# GW-RS485-V41-007.net
KiCad netlist of a schematic drawn in EAGLE
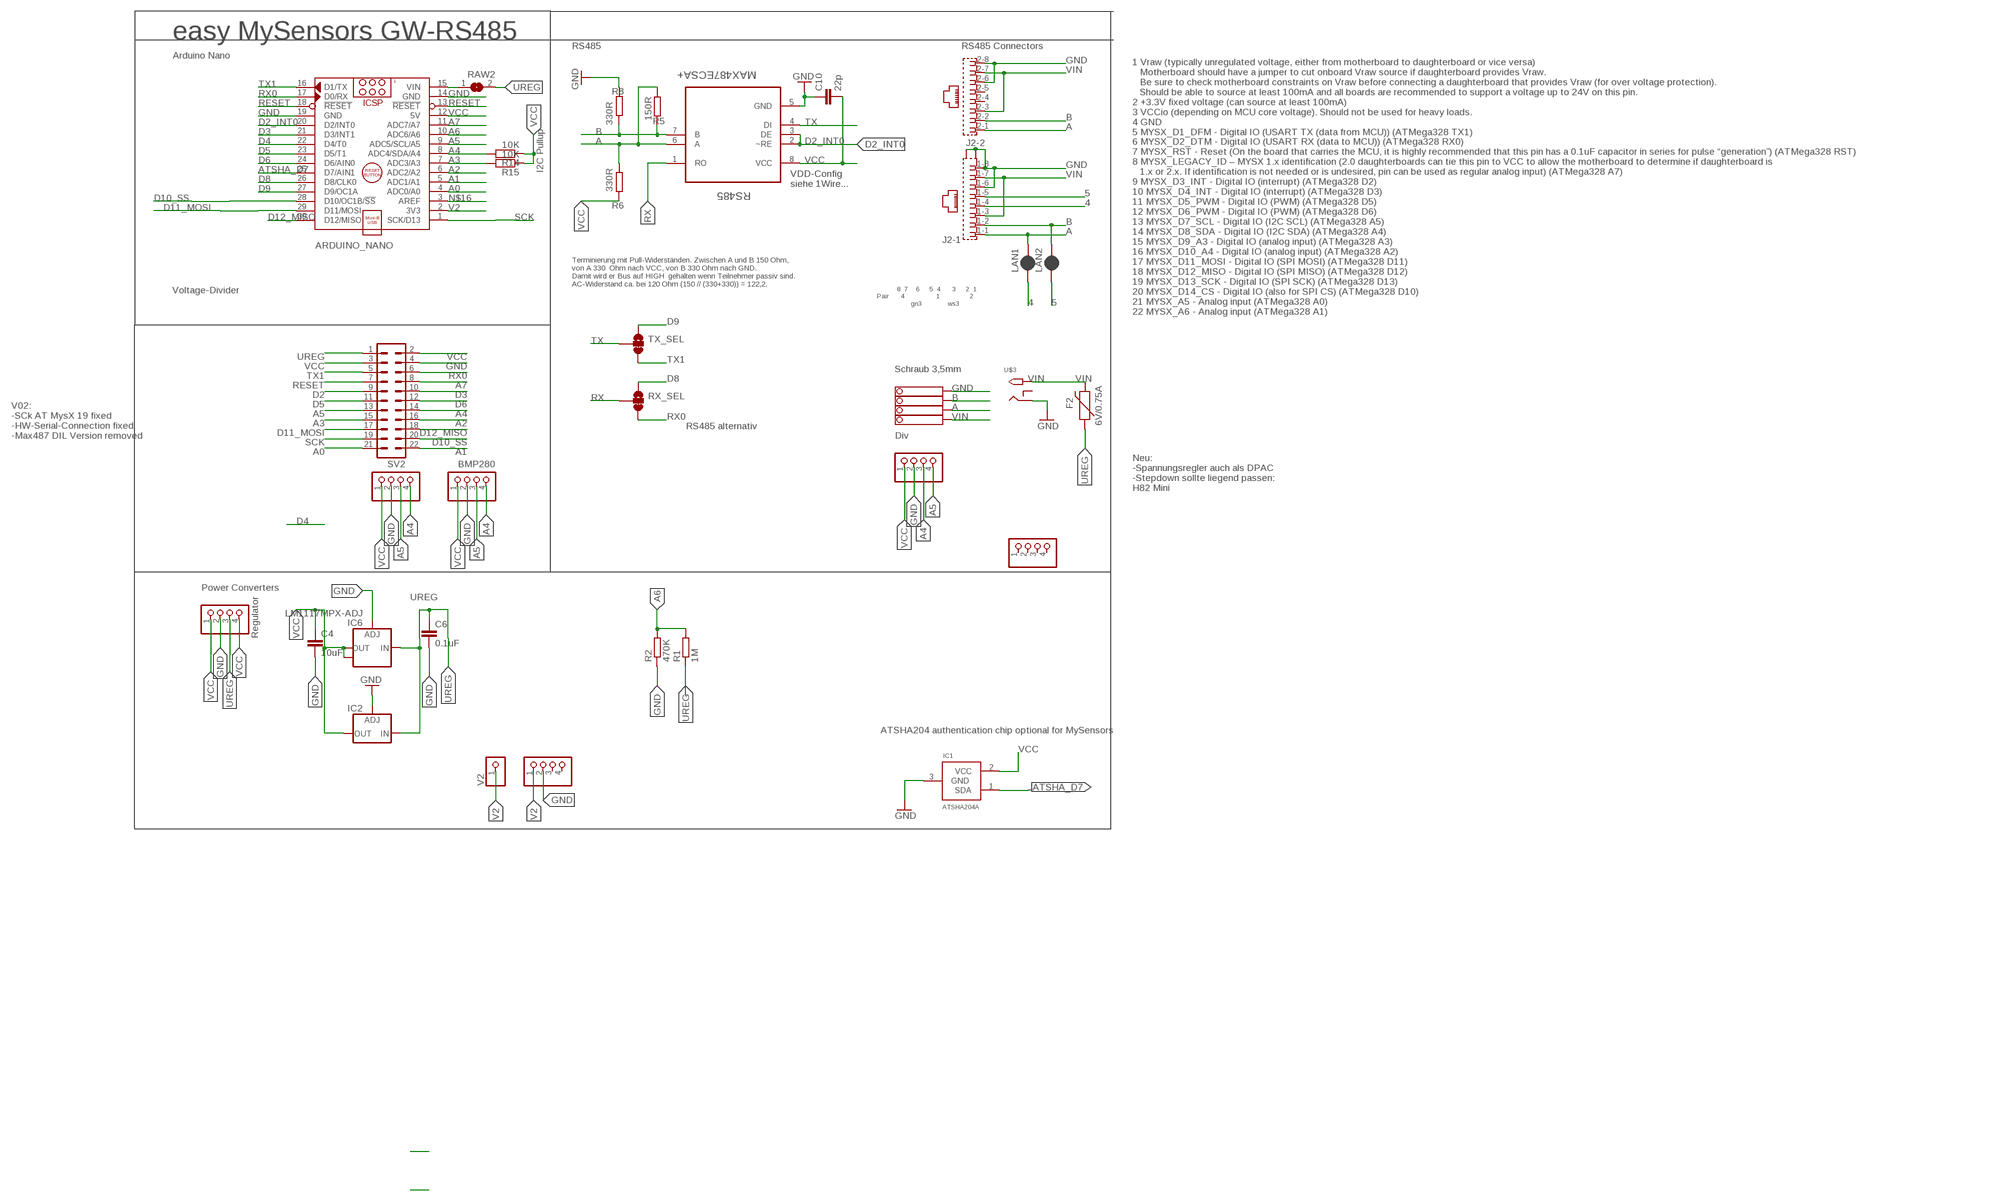
[diagram p0: schematic, sheet 1]

(export (version "E")
  (design (tool "Eeschema 10.0.6"))
  (components
    (comp (ref "ARDUINO_NANO")
      (value "ARDUINO_NANO_OHNE-BOHR")
      (footprint "eagle-import:ARDUINO_NANO")
      (libsource (lib "eagle-import") (part "ARDUINO_NANO_OHNE-BOHR"))
    )
    (comp (ref "BH1750")
      (value "PINHD-1X04_2.54-S")
      (footprint "eagle-import:1X04-S")
      (libsource (lib "eagle-import") (part "PINHD-1X04_2.54-S"))
    )
    (comp (ref "C4")
      (value "10uF")
      (footprint "eagle-import:C1210")
      (libsource (lib "eagle-import") (part "C-EUC1210"))
    )
    (comp (ref "C6")
      (value "0.1uF")
      (footprint "eagle-import:C1206")
      (libsource (lib "eagle-import") (part "C-EUC1206"))
    )
    (comp (ref "C10")
      (value "22p")
      (footprint "eagle-import:C0805")
      (libsource (lib "eagle-import") (part "C-EUC0805"))
    )
    (comp (ref "F2")
      (value "6V/0.75A")
      (footprint "eagle-import:1206")
      (libsource (lib "eagle-import") (part "PPTC_THREE-QUARTER-AMP"))
    )
    (comp (ref "I2C-1")
      (value "PINHD-1X04_2.54-S")
      (footprint "eagle-import:1X04-S")
      (libsource (lib "eagle-import") (part "PINHD-1X04_2.54-S"))
    )
    (comp (ref "I2C-2")
      (value "PINHD-1X04_2.54-S")
      (footprint "eagle-import:1X04-S")
      (libsource (lib "eagle-import") (part "PINHD-1X04_2.54-S"))
    )
    (comp (ref "IC1")
      (value "ATSHA204A")
      (footprint "eagle-import:SOT23")
      (libsource (lib "eagle-import") (part "ATSHA204A"))
    )
    (comp (ref "IC2")
      (value "LD117ADT50TR")
      (footprint "eagle-import:DPACK")
      (libsource (lib "eagle-import") (part "LD117A?DT50TR"))
    )
    (comp (ref "IC6")
      (value "LM1117MPX-ADJ")
      (footprint "eagle-import:SOT223")
      (libsource (lib "eagle-import") (part "LM1117MPX-ADJ"))
    )
    (comp (ref "J2")
      (value "RJ45_2X_S")
      (footprint "eagle-import:RJ45_2X_S")
      (libsource (lib "eagle-import") (part "RJ45_2X_S"))
    )
    (comp (ref "JP2")
      (value "PINHD-1X04_2.54-S")
      (footprint "eagle-import:1X04-S")
      (libsource (lib "eagle-import") (part "PINHD-1X04_2.54-S"))
    )
    (comp (ref "LAN1")
      (value "JUMPER-SMT_2_NC_PASTE_SILK")
      (footprint "eagle-import:SMT-JUMPER_2_NC_PASTE_SILK")
      (libsource (lib "eagle-import") (part "JUMPER-SMT_2_NC_PASTE_SILK"))
    )
    (comp (ref "LAN2")
      (value "JUMPER-SMT_2_NC_PASTE_SILK")
      (footprint "eagle-import:SMT-JUMPER_2_NC_PASTE_SILK")
      (libsource (lib "eagle-import") (part "JUMPER-SMT_2_NC_PASTE_SILK"))
    )
    (comp (ref "R1")
      (value "1M")
      (footprint "eagle-import:R0805")
      (libsource (lib "eagle-import") (part "R-EU_R0805"))
    )
    (comp (ref "R2")
      (value "470K")
      (footprint "eagle-import:R0805")
      (libsource (lib "eagle-import") (part "R-EU_R0805"))
    )
    (comp (ref "R5")
      (value "150R")
      (footprint "eagle-import:R0805")
      (libsource (lib "eagle-import") (part "R-EU_R0805"))
    )
    (comp (ref "R6")
      (value "330R")
      (footprint "eagle-import:R0805")
      (libsource (lib "eagle-import") (part "R-EU_R0805"))
    )
    (comp (ref "R8")
      (value "330R")
      (footprint "eagle-import:R0805")
      (libsource (lib "eagle-import") (part "R-EU_R0805"))
    )
    (comp (ref "R14")
      (value "10K")
      (footprint "eagle-import:R0805")
      (libsource (lib "eagle-import") (part "R-EU_R0805"))
    )
    (comp (ref "R15")
      (value "10K")
      (footprint "eagle-import:R0805")
      (libsource (lib "eagle-import") (part "R-EU_R0805"))
    )
    (comp (ref "RAW2")
      (value "SJ")
      (footprint "eagle-import:SJ")
      (libsource (lib "eagle-import") (part "SJ"))
    )
    (comp (ref "RS485")
      (value "MAX487ECSA+")
      (footprint "eagle-import:SOIC127P600X175-8N")
      (libsource (lib "eagle-import") (part "MAX487ECSA+"))
    )
    (comp (ref "RX_SEL")
      (value "JUMPER-SMT_3_1-NC_TRACE_SILK")
      (footprint "eagle-import:SMT-JUMPER_3_1-NC_TRACE_SILK")
      (libsource (lib "eagle-import") (part "JUMPER-SMT_3_1-NC_TRACE_SILK"))
    )
    (comp (ref "STEPDWN")
      (value "PINHD-1X04_2.54-S")
      (footprint "eagle-import:1X04-S")
      (libsource (lib "eagle-import") (part "PINHD-1X04_2.54-S"))
    )
    (comp (ref "SV2")
      (value "MA11-2")
      (footprint "eagle-import:MA11-2")
      (libsource (lib "eagle-import") (part "MA11-2"))
    )
    (comp (ref "TX_SEL")
      (value "JUMPER-SMT_3_1-NC_TRACE_SILK")
      (footprint "eagle-import:SMT-JUMPER_3_1-NC_TRACE_SILK")
      (libsource (lib "eagle-import") (part "JUMPER-SMT_3_1-NC_TRACE_SILK"))
    )
    (comp (ref "U$3")
      (value "2.1MMJACKTHM")
      (footprint "eagle-import:PJ-102A")
      (libsource (lib "eagle-import") (part "2.1MMJACKTHM"))
    )
    (comp (ref "V2")
      (value "PINHD-1X1")
      (footprint "eagle-import:1X01")
      (libsource (lib "eagle-import") (part "PINHD-1X1"))
    )
    (comp (ref "V2-")
      (value "PINHD-1X04_2.54-S")
      (footprint "eagle-import:1X04-S")
      (libsource (lib "eagle-import") (part "PINHD-1X04_2.54-S"))
    )
    (comp (ref "X4")
      (value "1751264")
      (footprint "eagle-import:1751264")
      (libsource (lib "eagle-import") (part "1751264"))
    )
  )
  (nets
    (net (code "1") (name "/4") (class "Default")
      (node (ref "J2") (pin "1-4") (pinfunction "4_1-4") (pintype "passive"))
      (node (ref "LAN1") (pin "1") (pinfunction "1_1") (pintype "passive"))
    )
    (net (code "2") (name "/5") (class "Default")
      (node (ref "J2") (pin "1-5") (pinfunction "5_1-5") (pintype "passive"))
      (node (ref "LAN2") (pin "1") (pinfunction "1_1") (pintype "passive"))
    )
    (net (code "3") (name "/A") (class "Default")
      (node (ref "J2") (pin "1-1") (pinfunction "1_1-1") (pintype "passive"))
      (node (ref "J2") (pin "2-1") (pinfunction "1_2-1") (pintype "passive"))
      (node (ref "LAN1") (pin "2") (pinfunction "2_2") (pintype "passive"))
      (node (ref "R5") (pin "1") (pinfunction "1_1") (pintype "passive"))
      (node (ref "R6") (pin "2") (pinfunction "2_2") (pintype "passive"))
      (node (ref "RS485") (pin "6") (pinfunction "A_6") (pintype "bidirectional"))
      (node (ref "X4") (pin "2") (pinfunction "K_2") (pintype "passive"))
    )
    (net (code "4") (name "/A0") (class "Default")
      (node (ref "ARDUINO_NANO") (pin "4") (pinfunction "ADC0/A0_4") (pintype "bidirectional"))
      (node (ref "SV2") (pin "21") (pinfunction "21_21") (pintype "passive"))
    )
    (net (code "5") (name "/A1") (class "Default")
      (node (ref "ARDUINO_NANO") (pin "5") (pinfunction "ADC1/A1_5") (pintype "bidirectional"))
      (node (ref "SV2") (pin "22") (pinfunction "22_22") (pintype "passive"))
    )
    (net (code "6") (name "/A2") (class "Default")
      (node (ref "ARDUINO_NANO") (pin "6") (pinfunction "ADC2/A2_6") (pintype "bidirectional"))
      (node (ref "SV2") (pin "16") (pinfunction "16_16") (pintype "passive"))
    )
    (net (code "7") (name "/A3") (class "Default")
      (node (ref "ARDUINO_NANO") (pin "7") (pinfunction "ADC3/A3_7") (pintype "bidirectional"))
      (node (ref "R15") (pin "2") (pinfunction "2_2") (pintype "passive"))
      (node (ref "SV2") (pin "15") (pinfunction "15_15") (pintype "passive"))
    )
    (net (code "8") (name "/A7") (class "Default")
      (node (ref "ARDUINO_NANO") (pin "11") (pinfunction "ADC7/A7_11") (pintype "bidirectional"))
      (node (ref "SV2") (pin "8") (pinfunction "8_8") (pintype "passive"))
    )
    (net (code "9") (name "/ATSHA_D7") (class "Default")
      (node (ref "ARDUINO_NANO") (pin "25") (pinfunction "D7/AIN1_25") (pintype "bidirectional"))
      (node (ref "IC1") (pin "1") (pinfunction "SDA_1") (pintype "bidirectional"))
    )
    (net (code "10") (name "/B") (class "Default")
      (node (ref "J2") (pin "1-2") (pinfunction "2_1-2") (pintype "passive"))
      (node (ref "J2") (pin "2-2") (pinfunction "2_2-2") (pintype "passive"))
      (node (ref "LAN2") (pin "2") (pinfunction "2_2") (pintype "passive"))
      (node (ref "R5") (pin "2") (pinfunction "2_2") (pintype "passive"))
      (node (ref "R8") (pin "1") (pinfunction "1_1") (pintype "passive"))
      (node (ref "RS485") (pin "7") (pinfunction "B_7") (pintype "bidirectional"))
      (node (ref "X4") (pin "3") (pinfunction "K_3") (pintype "passive"))
    )
    (net (code "11") (name "/D2") (class "Default")
      (node (ref "SV2") (pin "9") (pinfunction "9_9") (pintype "passive"))
    )
    (net (code "12") (name "/D3") (class "Default")
      (node (ref "ARDUINO_NANO") (pin "21") (pinfunction "D3/INT1_21") (pintype "bidirectional"))
      (node (ref "SV2") (pin "10") (pinfunction "10_10") (pintype "passive"))
    )
    (net (code "13") (name "/D4") (class "Default")
      (node (ref "ARDUINO_NANO") (pin "22") (pinfunction "D4/T0_22") (pintype "bidirectional"))
    )
    (net (code "14") (name "/D5") (class "Default")
      (node (ref "ARDUINO_NANO") (pin "23") (pinfunction "D5/T1_23") (pintype "bidirectional"))
      (node (ref "SV2") (pin "11") (pinfunction "11_11") (pintype "passive"))
    )
    (net (code "15") (name "/D6") (class "Default")
      (node (ref "ARDUINO_NANO") (pin "24") (pinfunction "D6/AIN0_24") (pintype "bidirectional"))
      (node (ref "SV2") (pin "12") (pinfunction "12_12") (pintype "passive"))
    )
    (net (code "16") (name "/D8") (class "Default")
      (node (ref "ARDUINO_NANO") (pin "26") (pinfunction "D8/CLK0_26") (pintype "bidirectional"))
      (node (ref "RX_SEL") (pin "1") (pinfunction "1_1") (pintype "passive"))
    )
    (net (code "17") (name "/D9") (class "Default")
      (node (ref "ARDUINO_NANO") (pin "27") (pinfunction "D9/OC1A_27") (pintype "bidirectional"))
      (node (ref "TX_SEL") (pin "1") (pinfunction "1_1") (pintype "passive"))
    )
    (net (code "18") (name "/D10_SS") (class "Default")
      (node (ref "ARDUINO_NANO") (pin "28") (pinfunction "D10/OC1B/~{SS}_28") (pintype "bidirectional"))
      (node (ref "SV2") (pin "20") (pinfunction "20_20") (pintype "passive"))
    )
    (net (code "19") (name "/D11_MOSI") (class "Default")
      (node (ref "ARDUINO_NANO") (pin "29") (pinfunction "D11/MOSI_29") (pintype "bidirectional"))
      (node (ref "SV2") (pin "17") (pinfunction "17_17") (pintype "passive"))
    )
    (net (code "20") (name "/D12_MISO") (class "Default")
      (node (ref "ARDUINO_NANO") (pin "30") (pinfunction "D12/MISO_30") (pintype "bidirectional"))
      (node (ref "SV2") (pin "18") (pinfunction "18_18") (pintype "passive"))
    )
    (net (code "21") (name "/N$16") (class "Default")
      (node (ref "ARDUINO_NANO") (pin "3") (pinfunction "AREF_3") (pintype "input"))
    )
    (net (code "22") (name "/RESET") (class "Default")
      (node (ref "ARDUINO_NANO") (pin "13") (pinfunction "~{RESET}_13") (pintype "input"))
      (node (ref "ARDUINO_NANO") (pin "18") (pinfunction "~{RESET}_18") (pintype "input"))
      (node (ref "SV2") (pin "7") (pinfunction "7_7") (pintype "passive"))
    )
    (net (code "23") (name "/RX0") (class "Default")
      (node (ref "ARDUINO_NANO") (pin "17") (pinfunction "D0/RX_17") (pintype "bidirectional"))
      (node (ref "RX_SEL") (pin "3") (pinfunction "3_3") (pintype "passive"))
      (node (ref "SV2") (pin "6") (pinfunction "6_6") (pintype "passive"))
    )
    (net (code "24") (name "/SCK") (class "Default")
      (node (ref "ARDUINO_NANO") (pin "1") (pinfunction "SCK/D13_1") (pintype "bidirectional"))
      (node (ref "SV2") (pin "19") (pinfunction "19_19") (pintype "passive"))
    )
    (net (code "25") (name "/TX") (class "Default")
      (node (ref "RS485") (pin "4") (pinfunction "DI_4") (pintype "input"))
      (node (ref "TX_SEL") (pin "2") (pinfunction "2_2") (pintype "passive"))
    )
    (net (code "26") (name "/TX1") (class "Default")
      (node (ref "ARDUINO_NANO") (pin "16") (pinfunction "D1/TX_16") (pintype "bidirectional"))
      (node (ref "SV2") (pin "5") (pinfunction "5_5") (pintype "passive"))
      (node (ref "TX_SEL") (pin "3") (pinfunction "3_3") (pintype "passive"))
    )
    (net (code "27") (name "/VIN") (class "Default")
      (node (ref "F2") (pin "2") (pinfunction "2_2") (pintype "bidirectional"))
      (node (ref "J2") (pin "1-3") (pinfunction "3_1-3") (pintype "passive"))
      (node (ref "J2") (pin "1-7") (pinfunction "7_1-7") (pintype "passive"))
      (node (ref "J2") (pin "2-3") (pinfunction "3_2-3") (pintype "passive"))
      (node (ref "J2") (pin "2-7") (pinfunction "7_2-7") (pintype "passive"))
      (node (ref "U$3") (pin "TIP") (pinfunction "TIP_TIP") (pintype "bidirectional"))
      (node (ref "X4") (pin "1") (pinfunction "K_1") (pintype "passive"))
    )
    (net (code "28") (name "A4") (class "Default")
      (node (ref "ARDUINO_NANO") (pin "8") (pinfunction "ADC4/SDA/A4_8") (pintype "bidirectional"))
      (node (ref "BH1750") (pin "4") (pinfunction "4_4") (pintype "passive"))
      (node (ref "I2C-1") (pin "4") (pinfunction "4_4") (pintype "passive"))
      (node (ref "I2C-2") (pin "3") (pinfunction "3_3") (pintype "passive"))
      (node (ref "R14") (pin "2") (pinfunction "2_2") (pintype "passive"))
      (node (ref "SV2") (pin "14") (pinfunction "14_14") (pintype "passive"))
    )
    (net (code "29") (name "A5") (class "Default")
      (node (ref "ARDUINO_NANO") (pin "9") (pinfunction "ADC5/SCL/A5_9") (pintype "bidirectional"))
      (node (ref "BH1750") (pin "3") (pinfunction "3_3") (pintype "passive"))
      (node (ref "I2C-1") (pin "3") (pinfunction "3_3") (pintype "passive"))
      (node (ref "I2C-2") (pin "4") (pinfunction "4_4") (pintype "passive"))
      (node (ref "SV2") (pin "13") (pinfunction "13_13") (pintype "passive"))
    )
    (net (code "30") (name "A6") (class "Default")
      (node (ref "ARDUINO_NANO") (pin "10") (pinfunction "ADC6/A6_10") (pintype "bidirectional"))
      (node (ref "R1") (pin "2") (pinfunction "2_2") (pintype "passive"))
      (node (ref "R2") (pin "2") (pinfunction "2_2") (pintype "passive"))
    )
    (net (code "31") (name "D2_INT0") (class "Default")
      (node (ref "ARDUINO_NANO") (pin "20") (pinfunction "D2/INT0_20") (pintype "bidirectional"))
      (node (ref "RS485") (pin "2") (pinfunction "~{RE}_2") (pintype "input"))
      (node (ref "RS485") (pin "3") (pinfunction "DE_3") (pintype "input"))
    )
    (net (code "32") (name "GND") (class "Default")
      (node (ref "ARDUINO_NANO") (pin "14") (pinfunction "GND_14") (pintype "power_in"))
      (node (ref "ARDUINO_NANO") (pin "19") (pinfunction "GND_19") (pintype "power_in"))
      (node (ref "BH1750") (pin "2") (pinfunction "2_2") (pintype "passive"))
      (node (ref "C10") (pin "1") (pinfunction "1_1") (pintype "passive"))
      (node (ref "C4") (pin "2") (pinfunction "2_2") (pintype "passive"))
      (node (ref "C6") (pin "2") (pinfunction "2_2") (pintype "passive"))
      (node (ref "I2C-1") (pin "2") (pinfunction "2_2") (pintype "passive"))
      (node (ref "I2C-2") (pin "2") (pinfunction "2_2") (pintype "passive"))
      (node (ref "IC1") (pin "3") (pinfunction "GND_3") (pintype "bidirectional"))
      (node (ref "IC2") (pin "1") (pinfunction "ADJ_1") (pintype "input"))
      (node (ref "IC6") (pin "1") (pinfunction "ADJ_1") (pintype "input"))
      (node (ref "J2") (pin "1-6") (pinfunction "6_1-6") (pintype "passive"))
      (node (ref "J2") (pin "1-8") (pinfunction "8_1-8") (pintype "passive"))
      (node (ref "J2") (pin "2-6") (pinfunction "6_2-6") (pintype "passive"))
      (node (ref "J2") (pin "2-8") (pinfunction "8_2-8") (pintype "passive"))
      (node (ref "J2") (pin "G1") (pinfunction "S2_G1") (pintype "passive"))
      (node (ref "J2") (pin "G3") (pinfunction "S1_G3") (pintype "passive"))
      (node (ref "R2") (pin "1") (pinfunction "1_1") (pintype "passive"))
      (node (ref "R8") (pin "2") (pinfunction "2_2") (pintype "passive"))
      (node (ref "RS485") (pin "5") (pinfunction "GND_5") (pintype "passive"))
      (node (ref "STEPDWN") (pin "2") (pinfunction "2_2") (pintype "passive"))
      (node (ref "SV2") (pin "4") (pinfunction "4_4") (pintype "passive"))
      (node (ref "U$3") (pin "RING") (pinfunction "RING_RING") (pintype "bidirectional"))
      (node (ref "V2-") (pin "2") (pinfunction "2_2") (pintype "passive"))
      (node (ref "X4") (pin "4") (pinfunction "K_4") (pintype "passive"))
    )
    (net (code "33") (name "Net-(ARDUINO_NANO-VIN)") (class "Default")
      (node (ref "ARDUINO_NANO") (pin "15") (pinfunction "VIN_15") (pintype "power_in"))
      (node (ref "RAW2") (pin "1") (pinfunction "1_1") (pintype "passive"))
    )
    (net (code "34") (name "RX") (class "Default")
      (node (ref "RS485") (pin "1") (pinfunction "RO_1") (pintype "output"))
      (node (ref "RX_SEL") (pin "2") (pinfunction "2_2") (pintype "passive"))
    )
    (net (code "35") (name "UREG") (class "Default")
      (node (ref "C6") (pin "1") (pinfunction "1_1") (pintype "passive"))
      (node (ref "F2") (pin "1") (pinfunction "1_1") (pintype "bidirectional"))
      (node (ref "IC2") (pin "3") (pinfunction "IN_3") (pintype "input"))
      (node (ref "IC6") (pin "3") (pinfunction "IN_3") (pintype "input"))
      (node (ref "R1") (pin "1") (pinfunction "1_1") (pintype "passive"))
      (node (ref "RAW2") (pin "2") (pinfunction "2_2") (pintype "passive"))
      (node (ref "STEPDWN") (pin "3") (pinfunction "3_3") (pintype "passive"))
      (node (ref "SV2") (pin "1") (pinfunction "1_1") (pintype "passive"))
    )
    (net (code "36") (name "V2") (class "Default")
      (node (ref "ARDUINO_NANO") (pin "2") (pinfunction "3V3_2") (pintype "output"))
      (node (ref "V2") (pin "1") (pinfunction "1_1") (pintype "passive"))
      (node (ref "V2-") (pin "1") (pinfunction "1_1") (pintype "passive"))
    )
    (net (code "37") (name "VCC") (class "Default")
      (node (ref "ARDUINO_NANO") (pin "12") (pinfunction "5V_12") (pintype "power_in"))
      (node (ref "BH1750") (pin "1") (pinfunction "1_1") (pintype "passive"))
      (node (ref "C10") (pin "2") (pinfunction "2_2") (pintype "passive"))
      (node (ref "C4") (pin "1") (pinfunction "1_1") (pintype "passive"))
      (node (ref "I2C-1") (pin "1") (pinfunction "1_1") (pintype "passive"))
      (node (ref "I2C-2") (pin "1") (pinfunction "1_1") (pintype "passive"))
      (node (ref "IC1") (pin "2") (pinfunction "VCC_2") (pintype "bidirectional"))
      (node (ref "IC2") (pin "4") (pinfunction "OUT_4") (pintype "passive"))
      (node (ref "IC6") (pin "2") (pinfunction "OUT_2") (pintype "passive"))
      (node (ref "IC6") (pin "TAB") (pinfunction "OUT1_TAB") (pintype "passive"))
      (node (ref "R14") (pin "1") (pinfunction "1_1") (pintype "passive"))
      (node (ref "R15") (pin "1") (pinfunction "1_1") (pintype "passive"))
      (node (ref "R6") (pin "1") (pinfunction "1_1") (pintype "passive"))
      (node (ref "RS485") (pin "8") (pinfunction "VCC_8") (pintype "power_in"))
      (node (ref "STEPDWN") (pin "1") (pinfunction "1_1") (pintype "passive"))
      (node (ref "STEPDWN") (pin "4") (pinfunction "4_4") (pintype "passive"))
      (node (ref "SV2") (pin "2") (pinfunction "2_2") (pintype "passive"))
      (node (ref "SV2") (pin "3") (pinfunction "3_3") (pintype "passive"))
    )
    (net (code "38") (name "unconnected-(J2B-4-Pad2-4)") (class "Default")
      (node (ref "J2") (pin "2-4") (pinfunction "4_2-4") (pintype "passive"))
    )
    (net (code "39") (name "unconnected-(J2B-5-Pad2-5)") (class "Default")
      (node (ref "J2") (pin "2-5") (pinfunction "5_2-5") (pintype "passive"))
    )
    (net (code "40") (name "unconnected-(JP2-Pad1)") (class "Default")
      (node (ref "JP2") (pin "1") (pinfunction "1_1") (pintype "passive"))
    )
    (net (code "41") (name "unconnected-(JP2-Pad2)") (class "Default")
      (node (ref "JP2") (pin "2") (pinfunction "2_2") (pintype "passive"))
    )
    (net (code "42") (name "unconnected-(JP2-Pad3)") (class "Default")
      (node (ref "JP2") (pin "3") (pinfunction "3_3") (pintype "passive"))
    )
    (net (code "43") (name "unconnected-(JP2-Pad4)") (class "Default")
      (node (ref "JP2") (pin "4") (pinfunction "4_4") (pintype "passive"))
    )
    (net (code "44") (name "unconnected-(U$3-PadRING_SW)") (class "Default")
      (node (ref "U$3") (pin "RING_SW") (pinfunction "RING_SW_RING_SW") (pintype "bidirectional"))
    )
    (net (code "45") (name "unconnected-(V2--Pad3)") (class "Default")
      (node (ref "V2-") (pin "3") (pinfunction "3_3") (pintype "passive"))
    )
    (net (code "46") (name "unconnected-(V2--Pad4)") (class "Default")
      (node (ref "V2-") (pin "4") (pinfunction "4_4") (pintype "passive"))
    )
  )
)
